# Reid_Orthotic_v2_MCU.net
KiCad netlist of a schematic drawn in Altium Designer
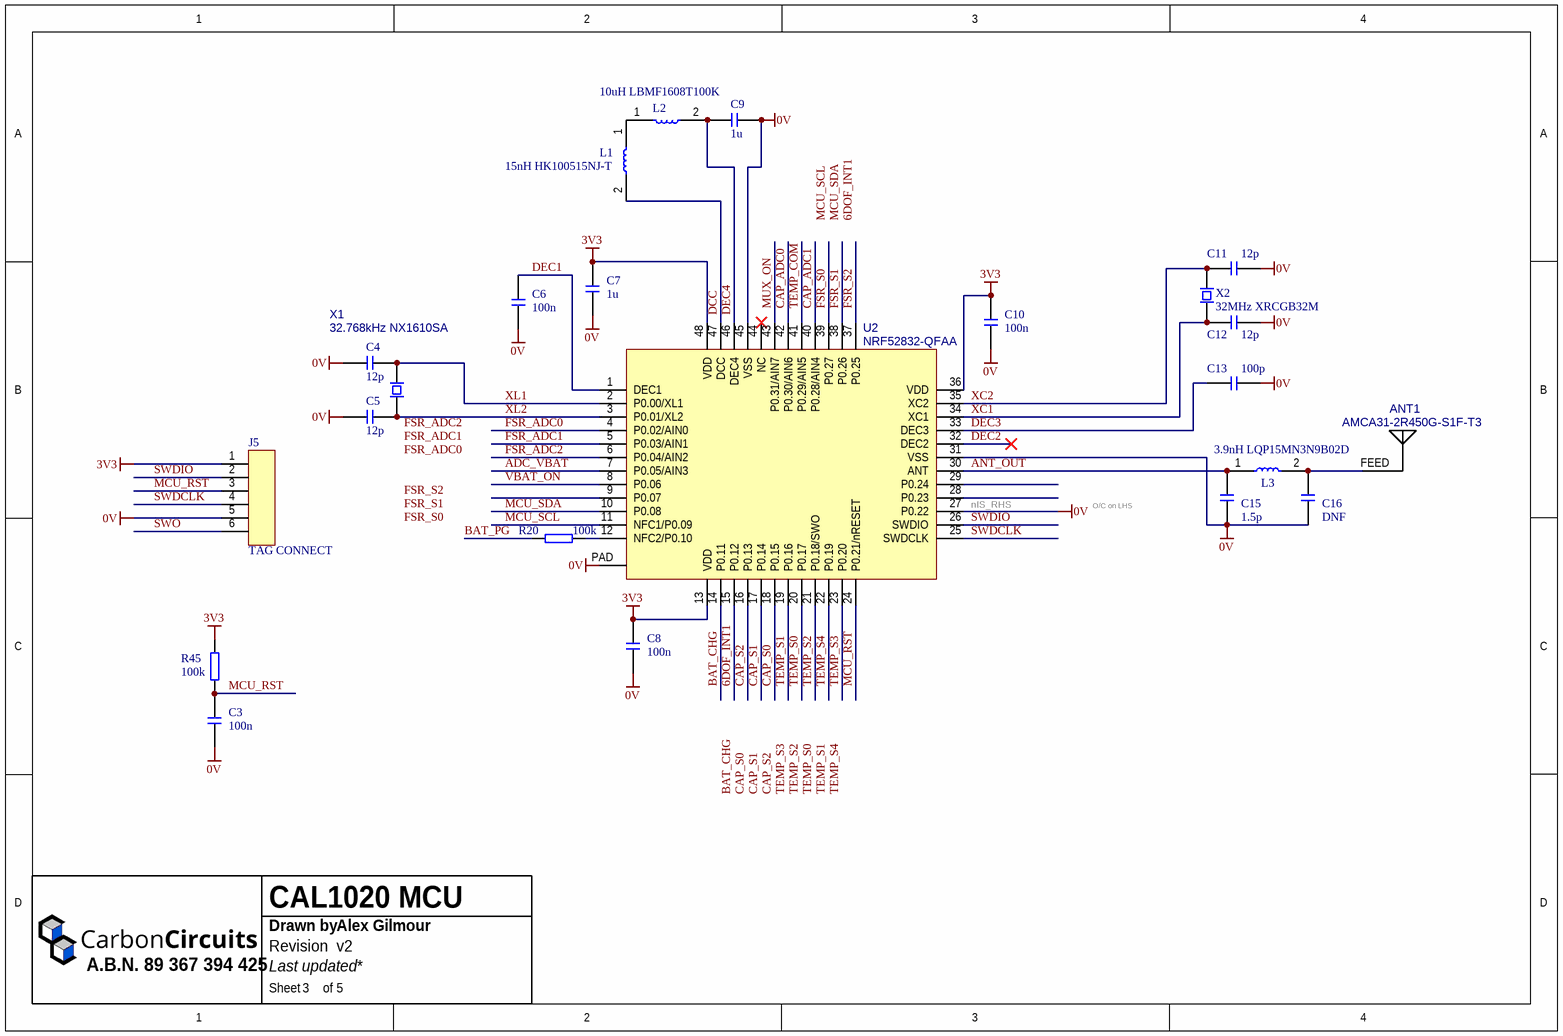
[diagram p0: Reid Orthotic v2 MCU.SchDoc]

(export (version "E")
  (design (tool "Eeschema 10.0.6"))
  (components
    (comp (ref "ANT1")
      (value "AMCA31-2R450G-S1F-T3")
      (footprint "RFANT3216120A5T")
      (libsource (lib "Canaria v5 Library") (part "Antenna"))
    )
    (comp (ref "C3")
      (value "100n")
      (footprint "0402 CAP HD")
      (libsource (lib "zoo589 PCB Library") (part "Capacitor"))
    )
    (comp (ref "C4")
      (value "12p")
      (footprint "0402 CAP HD")
      (libsource (lib "zoo589 PCB Library") (part "Capacitor"))
    )
    (comp (ref "C5")
      (value "12p")
      (footprint "0402 CAP HD")
      (libsource (lib "zoo589 PCB Library") (part "Capacitor"))
    )
    (comp (ref "C6")
      (value "100n")
      (footprint "0402 CAP HD")
      (libsource (lib "zoo589 PCB Library") (part "Capacitor"))
    )
    (comp (ref "C7")
      (value "1u")
      (footprint "0402 CAP HD")
      (libsource (lib "zoo589 PCB Library") (part "Capacitor"))
    )
    (comp (ref "C8")
      (value "100n")
      (footprint "0402 CAP HD")
      (libsource (lib "zoo589 PCB Library") (part "Capacitor"))
    )
    (comp (ref "C9")
      (value "1u")
      (footprint "0402 CAP HD")
      (libsource (lib "zoo589 PCB Library") (part "Capacitor"))
    )
    (comp (ref "C10")
      (value "100n")
      (footprint "0402 CAP HD")
      (libsource (lib "zoo589 PCB Library") (part "Capacitor"))
    )
    (comp (ref "C11")
      (value "12p")
      (footprint "0402 CAP HD")
      (libsource (lib "zoo589 PCB Library") (part "Capacitor"))
    )
    (comp (ref "C12")
      (value "12p")
      (footprint "0402 CAP HD")
      (libsource (lib "zoo589 PCB Library") (part "Capacitor"))
    )
    (comp (ref "C13")
      (value "100p")
      (footprint "0402 CAP HD")
      (libsource (lib "zoo589 PCB Library") (part "Capacitor"))
    )
    (comp (ref "C15")
      (value "1.5p")
      (footprint "0402 CAP HD")
      (libsource (lib "zoo589 PCB Library") (part "Capacitor"))
    )
    (comp (ref "C16")
      (value "DNF")
      (footprint "0402 CAP HD")
      (libsource (lib "zoo589 PCB Library") (part "Capacitor"))
    )
    (comp (ref "J5")
      (value "TAG CONNECT")
      (footprint "TC2030-NL")
      (libsource (lib "CarbonCircuits Part Library") (part "CON 6POS"))
    )
    (comp (ref "L1")
      (value "15nH HK100515NJ-T")
      (footprint "0402 HD")
      (libsource (lib "zoo589 PCB Library") (part "Inductor"))
    )
    (comp (ref "L2")
      (value "10uH LBMF1608T100K")
      (footprint "0603 HD")
      (libsource (lib "zoo589 PCB Library") (part "Inductor"))
    )
    (comp (ref "L3")
      (value "3.9nH LQP15MN3N9B02D")
      (footprint "0402 HD")
      (libsource (lib "") (part "Inductor_1"))
    )
    (comp (ref "R20")
      (value "100k")
      (footprint "0402 RES HD")
      (libsource (lib "zoo589 PCB Library") (part "Resistor"))
    )
    (comp (ref "R45")
      (value "100k")
      (footprint "0402 RES HD")
      (libsource (lib "zoo589 PCB Library") (part "Resistor"))
    )
    (comp (ref "U2")
      (value "NRF52832-QFAA")
      (footprint "NRF52832-QFAA")
      (libsource (lib "Canaria v5 Library") (part "NRF52832-QFAA"))
    )
    (comp (ref "X1")
      (value "32.768kHz NX1610SA")
      (footprint "CRYSTAL NDK NX1610SA")
      (libsource (lib "Earthoffset Prototype v1 PCB Library") (part "Crystal 32.768kHz"))
    )
    (comp (ref "X2")
      (value "32MHz XRCGB32M")
      (footprint "XTAL 2016")
      (libsource (lib "zoo589 PCB Library") (part "Crystal"))
    )
  )
  (nets
    (net (code "1") (name "/6DOF_INT1") (class "Default")
      (node (ref "U2") (pin "15") (pinfunction "P0.12_15") (pintype "passive"))
    )
    (net (code "2") (name "/ADC_VBAT") (class "Default")
      (node (ref "U2") (pin "7") (pinfunction "P0.05/AIN3_7") (pintype "passive"))
    )
    (net (code "3") (name "/ANT_OUT") (class "Default")
      (node (ref "C15") (pin "2") (pinfunction "2_2") (pintype "passive"))
      (node (ref "L3") (pin "1") (pinfunction "1_1") (pintype "passive"))
      (node (ref "U2") (pin "30") (pinfunction "ANT_30") (pintype "passive"))
    )
    (net (code "4") (name "/BAT_CHG") (class "Default")
      (node (ref "U2") (pin "14") (pinfunction "P0.11_14") (pintype "passive"))
    )
    (net (code "5") (name "/BAT_PG") (class "Default")
      (node (ref "R20") (pin "2") (pinfunction "2_2") (pintype "passive"))
    )
    (net (code "6") (name "/CAP_ADC0") (class "Default")
      (node (ref "U2") (pin "42") (pinfunction "P0.30/AIN6_42") (pintype "passive"))
    )
    (net (code "7") (name "/CAP_ADC1") (class "Default")
      (node (ref "U2") (pin "40") (pinfunction "P0.28/AIN4_40") (pintype "passive"))
    )
    (net (code "8") (name "/CAP_S0") (class "Default")
      (node (ref "U2") (pin "18") (pinfunction "P0.15_18") (pintype "passive"))
    )
    (net (code "9") (name "/CAP_S1") (class "Default")
      (node (ref "U2") (pin "17") (pinfunction "P0.14_17") (pintype "passive"))
    )
    (net (code "10") (name "/CAP_S2") (class "Default")
      (node (ref "U2") (pin "16") (pinfunction "P0.13_16") (pintype "passive"))
    )
    (net (code "11") (name "/DCC") (class "Default")
      (node (ref "L1") (pin "2") (pinfunction "2_2") (pintype "passive"))
      (node (ref "U2") (pin "47") (pinfunction "DCC_47") (pintype "passive"))
    )
    (net (code "12") (name "/DEC1") (class "Default")
      (node (ref "C6") (pin "2") (pinfunction "2_2") (pintype "passive"))
      (node (ref "U2") (pin "1") (pinfunction "DEC1_1") (pintype "passive"))
    )
    (net (code "13") (name "/DEC2") (class "Default")
      (node (ref "U2") (pin "32") (pinfunction "DEC2_32") (pintype "passive+no_connect"))
    )
    (net (code "14") (name "/DEC3") (class "Default")
      (node (ref "C13") (pin "2") (pinfunction "2_2") (pintype "passive"))
      (node (ref "U2") (pin "33") (pinfunction "DEC3_33") (pintype "passive"))
    )
    (net (code "15") (name "/DEC4") (class "Default")
      (node (ref "C9") (pin "2") (pinfunction "2_2") (pintype "passive"))
      (node (ref "L2") (pin "2") (pinfunction "2_2") (pintype "passive"))
      (node (ref "U2") (pin "46") (pinfunction "DEC4_46") (pintype "passive"))
    )
    (net (code "16") (name "/FSR_ADC0") (class "Default")
      (node (ref "U2") (pin "4") (pinfunction "P0.02/AIN0_4") (pintype "passive"))
    )
    (net (code "17") (name "/FSR_ADC1") (class "Default")
      (node (ref "U2") (pin "5") (pinfunction "P0.03/AIN1_5") (pintype "passive"))
    )
    (net (code "18") (name "/FSR_ADC2") (class "Default")
      (node (ref "U2") (pin "6") (pinfunction "P0.04/AIN2_6") (pintype "passive"))
    )
    (net (code "19") (name "/FSR_S0") (class "Default")
      (node (ref "U2") (pin "39") (pinfunction "P0.27_39") (pintype "passive"))
    )
    (net (code "20") (name "/FSR_S1") (class "Default")
      (node (ref "U2") (pin "38") (pinfunction "P0.26_38") (pintype "passive"))
    )
    (net (code "21") (name "/FSR_S2") (class "Default")
      (node (ref "U2") (pin "37") (pinfunction "P0.25_37") (pintype "passive"))
    )
    (net (code "22") (name "/MCU_RST") (class "Default")
      (node (ref "C3") (pin "2") (pinfunction "2_2") (pintype "passive"))
      (node (ref "J5") (pin "3") (pinfunction "3_3") (pintype "passive"))
      (node (ref "R45") (pin "1") (pinfunction "1_1") (pintype "passive"))
      (node (ref "U2") (pin "24") (pinfunction "P0.21/nRESET_24") (pintype "passive"))
    )
    (net (code "23") (name "/MCU_SCL") (class "Default")
      (node (ref "U2") (pin "11") (pinfunction "NFC1/P0.09_11") (pintype "passive"))
    )
    (net (code "24") (name "/MCU_SDA") (class "Default")
      (node (ref "U2") (pin "10") (pinfunction "P0.08_10") (pintype "passive"))
    )
    (net (code "25") (name "/MUX_ON") (class "Default")
      (node (ref "U2") (pin "43") (pinfunction "P0.31/AIN7_43") (pintype "passive"))
    )
    (net (code "26") (name "/SWDCLK") (class "Default")
      (node (ref "J5") (pin "4") (pinfunction "4_4") (pintype "passive"))
      (node (ref "U2") (pin "25") (pinfunction "SWDCLK_25") (pintype "passive"))
    )
    (net (code "27") (name "/SWDIO") (class "Default")
      (node (ref "J5") (pin "2") (pinfunction "2_2") (pintype "passive"))
      (node (ref "U2") (pin "26") (pinfunction "SWDIO_26") (pintype "passive"))
    )
    (net (code "28") (name "/SWO") (class "Default")
      (node (ref "J5") (pin "6") (pinfunction "6_6") (pintype "passive"))
    )
    (net (code "29") (name "/TEMP_COM") (class "Default")
      (node (ref "U2") (pin "41") (pinfunction "P0.29/AIN5_41") (pintype "passive"))
    )
    (net (code "30") (name "/TEMP_S0") (class "Default")
      (node (ref "U2") (pin "20") (pinfunction "P0.17_20") (pintype "passive"))
    )
    (net (code "31") (name "/TEMP_S1") (class "Default")
      (node (ref "U2") (pin "19") (pinfunction "P0.16_19") (pintype "passive"))
    )
    (net (code "32") (name "/TEMP_S2") (class "Default")
      (node (ref "U2") (pin "21") (pinfunction "P0.18/SWO_21") (pintype "passive"))
    )
    (net (code "33") (name "/TEMP_S3") (class "Default")
      (node (ref "U2") (pin "23") (pinfunction "P0.20_23") (pintype "passive"))
    )
    (net (code "34") (name "/TEMP_S4") (class "Default")
      (node (ref "U2") (pin "22") (pinfunction "P0.19_22") (pintype "passive"))
    )
    (net (code "35") (name "/VBAT_ON") (class "Default")
      (node (ref "U2") (pin "8") (pinfunction "P0.06_8") (pintype "passive"))
    )
    (net (code "36") (name "/XC1") (class "Default")
      (node (ref "C12") (pin "2") (pinfunction "2_2") (pintype "passive"))
      (node (ref "U2") (pin "34") (pinfunction "XC1_34") (pintype "passive"))
      (node (ref "X2") (pin "1") (pinfunction "1_1") (pintype "passive"))
    )
    (net (code "37") (name "/XC2") (class "Default")
      (node (ref "C11") (pin "2") (pinfunction "2_2") (pintype "passive"))
      (node (ref "U2") (pin "35") (pinfunction "XC2_35") (pintype "passive"))
      (node (ref "X2") (pin "2") (pinfunction "2_2") (pintype "passive"))
    )
    (net (code "38") (name "/XL1") (class "Default")
      (node (ref "C4") (pin "1") (pinfunction "1_1") (pintype "passive"))
      (node (ref "U2") (pin "2") (pinfunction "P0.00/XL1_2") (pintype "passive"))
      (node (ref "X1") (pin "1") (pinfunction "1_1") (pintype "passive"))
    )
    (net (code "39") (name "/XL2") (class "Default")
      (node (ref "C5") (pin "1") (pinfunction "1_1") (pintype "passive"))
      (node (ref "U2") (pin "3") (pinfunction "P0.01/XL2_3") (pintype "passive"))
      (node (ref "X1") (pin "2") (pinfunction "2_2") (pintype "passive"))
    )
    (net (code "40") (name "0V") (class "Default")
      (node (ref "C10") (pin "1") (pinfunction "1_1") (pintype "passive"))
      (node (ref "C11") (pin "1") (pinfunction "1_1") (pintype "passive"))
      (node (ref "C12") (pin "1") (pinfunction "1_1") (pintype "passive"))
      (node (ref "C13") (pin "1") (pinfunction "1_1") (pintype "passive"))
      (node (ref "C15") (pin "1") (pinfunction "1_1") (pintype "passive"))
      (node (ref "C16") (pin "1") (pinfunction "1_1") (pintype "passive"))
      (node (ref "C3") (pin "1") (pinfunction "1_1") (pintype "passive"))
      (node (ref "C4") (pin "2") (pinfunction "2_2") (pintype "passive"))
      (node (ref "C5") (pin "2") (pinfunction "2_2") (pintype "passive"))
      (node (ref "C6") (pin "1") (pinfunction "1_1") (pintype "passive"))
      (node (ref "C7") (pin "1") (pinfunction "1_1") (pintype "passive"))
      (node (ref "C8") (pin "1") (pinfunction "1_1") (pintype "passive"))
      (node (ref "C9") (pin "1") (pinfunction "1_1") (pintype "passive"))
      (node (ref "J5") (pin "5") (pinfunction "5_5") (pintype "passive"))
      (node (ref "U2") (pin "27") (pinfunction "P0.22_27") (pintype "passive"))
      (node (ref "U2") (pin "31") (pinfunction "VSS_31") (pintype "passive"))
      (node (ref "U2") (pin "45") (pinfunction "VSS_45") (pintype "passive"))
      (node (ref "U2") (pin "PAD") (pinfunction "PAD_PAD") (pintype "passive"))
    )
    (net (code "41") (name "3V3") (class "Default")
      (node (ref "C10") (pin "2") (pinfunction "2_2") (pintype "passive"))
      (node (ref "C7") (pin "2") (pinfunction "2_2") (pintype "passive"))
      (node (ref "C8") (pin "2") (pinfunction "2_2") (pintype "passive"))
      (node (ref "J5") (pin "1") (pinfunction "1_1") (pintype "passive"))
      (node (ref "R45") (pin "2") (pinfunction "2_2") (pintype "passive"))
      (node (ref "U2") (pin "13") (pinfunction "VDD_13") (pintype "passive"))
      (node (ref "U2") (pin "36") (pinfunction "VDD_36") (pintype "passive"))
      (node (ref "U2") (pin "48") (pinfunction "VDD_48") (pintype "passive"))
    )
    (net (code "42") (name "Net-(ANT1-PadFEED)") (class "Default")
      (node (ref "ANT1") (pin "FEED") (pinfunction "FEED_FEED") (pintype "passive"))
      (node (ref "C16") (pin "2") (pinfunction "2_2") (pintype "passive"))
      (node (ref "L3") (pin "2") (pinfunction "2_2") (pintype "passive"))
    )
    (net (code "43") (name "Net-(L1-Pad1)") (class "Default")
      (node (ref "L1") (pin "1") (pinfunction "1_1") (pintype "passive"))
      (node (ref "L2") (pin "1") (pinfunction "1_1") (pintype "passive"))
    )
    (net (code "44") (name "Net-(U2-NFC2{slash}P0.10)") (class "Default")
      (node (ref "R20") (pin "1") (pinfunction "1_1") (pintype "passive"))
      (node (ref "U2") (pin "12") (pinfunction "NFC2/P0.10_12") (pintype "passive"))
    )
    (net (code "45") (name "unconnected-(U2-NC-Pad44)") (class "Default")
      (node (ref "U2") (pin "44") (pinfunction "NC_44") (pintype "passive+no_connect"))
    )
    (net (code "46") (name "unconnected-(U2-P0.07-Pad9)") (class "Default")
      (node (ref "U2") (pin "9") (pinfunction "P0.07_9") (pintype "passive"))
    )
    (net (code "47") (name "unconnected-(U2-P0.23-Pad28)") (class "Default")
      (node (ref "U2") (pin "28") (pinfunction "P0.23_28") (pintype "passive"))
    )
    (net (code "48") (name "unconnected-(U2-P0.24-Pad29)") (class "Default")
      (node (ref "U2") (pin "29") (pinfunction "P0.24_29") (pintype "passive"))
    )
  )
)
